# sema.net
KiCad netlist of a schematic drawn in Altium Designer
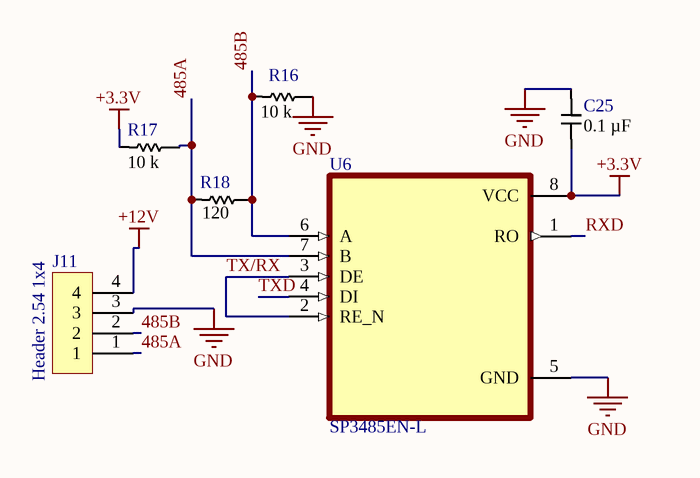
[diagram p0: sema.SchDoc]

(export (version "E")
  (design (tool "Eeschema 10.0.6"))
  (components
    (comp (ref "C25")
      (value "0.1uF")
      (footprint "SAMSUNG_CAP_0805_095")
      (description "CAP CER 0.1UF 25V X7R 0805")
      (fields (field (name "CAPACITANCE") "0.1 µF"))
      (libsource (lib "ilk") (part "0.1uF"))
    )
    (comp (ref "J11")
      (value "Header 2.54 1x4")
      (footprint "Header 2.54 1x4")
      (libsource (lib "ilk") (part "Header 2.54 1x4"))
    )
    (comp (ref "R16")
      (value "10k")
      (footprint "ROYALOHM_RES_0805")
      (description "RES SMD 10K OHM 1% 1/8W 0805")
      (fields (field (name "RESISTANCE") "10 k"))
      (libsource (lib "ilk") (part "10k"))
    )
    (comp (ref "R17")
      (value "10k")
      (footprint "ROYALOHM_RES_0805")
      (description "RES SMD 10K OHM 1% 1/8W 0805")
      (fields (field (name "RESISTANCE") "10 k"))
      (libsource (lib "ilk") (part "10k"))
    )
    (comp (ref "R18")
      (value "0805S8F1000T5E")
      (footprint "ROYALOHM_RES_0805")
      (description "RES SMD 100R OHM 1% 1/8W 0805")
      (fields (field (name "RESISTANCE") "120"))
      (libsource (lib "ilk") (part "0805S8F1000T5E"))
    )
    (comp (ref "U6")
      (value "SP3485EN-L")
      (footprint "SP3485EN-L:SOIC127P600X175-8N")
      (fields (field (name "MF") "{'manufacturer': u'MaxLinear, Inc.'}"))
      (libsource (lib "ilk") (part "SP3485EN-L"))
    )
  )
  (nets
    (net (code "1") (name "+3.3V") (class "Default")
      (node (ref "C25") (pin "1") (pinfunction "1_1") (pintype "passive"))
      (node (ref "R17") (pin "1") (pinfunction "1_1") (pintype "passive"))
      (node (ref "U6") (pin "8") (pinfunction "VCC_8") (pintype "power_in"))
    )
    (net (code "2") (name "+12V") (class "Default")
      (node (ref "J11") (pin "4") (pinfunction "4_4") (pintype "passive"))
    )
    (net (code "3") (name "/485A") (class "Default")
      (node (ref "J11") (pin "1") (pinfunction "1_1") (pintype "passive"))
      (node (ref "R17") (pin "2") (pinfunction "2_2") (pintype "passive"))
      (node (ref "R18") (pin "1") (pinfunction "1_1") (pintype "passive"))
      (node (ref "U6") (pin "7") (pinfunction "B_7") (pintype "input"))
    )
    (net (code "4") (name "/485B") (class "Default")
      (node (ref "J11") (pin "2") (pinfunction "2_2") (pintype "passive"))
      (node (ref "R16") (pin "1") (pinfunction "1_1") (pintype "passive"))
      (node (ref "R18") (pin "2") (pinfunction "2_2") (pintype "passive"))
      (node (ref "U6") (pin "6") (pinfunction "A_6") (pintype "input"))
    )
    (net (code "5") (name "/RXD") (class "Default")
      (node (ref "U6") (pin "1") (pinfunction "RO_1") (pintype "output"))
    )
    (net (code "6") (name "/TXD") (class "Default")
      (node (ref "U6") (pin "4") (pinfunction "DI_4") (pintype "input"))
    )
    (net (code "7") (name "/TX{slash}RX") (class "Default")
      (node (ref "U6") (pin "2") (pinfunction "RE_N_2") (pintype "input"))
      (node (ref "U6") (pin "3") (pinfunction "DE_3") (pintype "input"))
    )
    (net (code "8") (name "GND") (class "Default")
      (node (ref "C25") (pin "2") (pinfunction "2_2") (pintype "passive"))
      (node (ref "J11") (pin "3") (pinfunction "3_3") (pintype "passive"))
      (node (ref "R16") (pin "2") (pinfunction "2_2") (pintype "passive"))
      (node (ref "U6") (pin "5") (pinfunction "GND_5") (pintype "power_in"))
    )
  )
)
